# core09ss.net
KiCad netlist of a schematic drawn in EAGLE
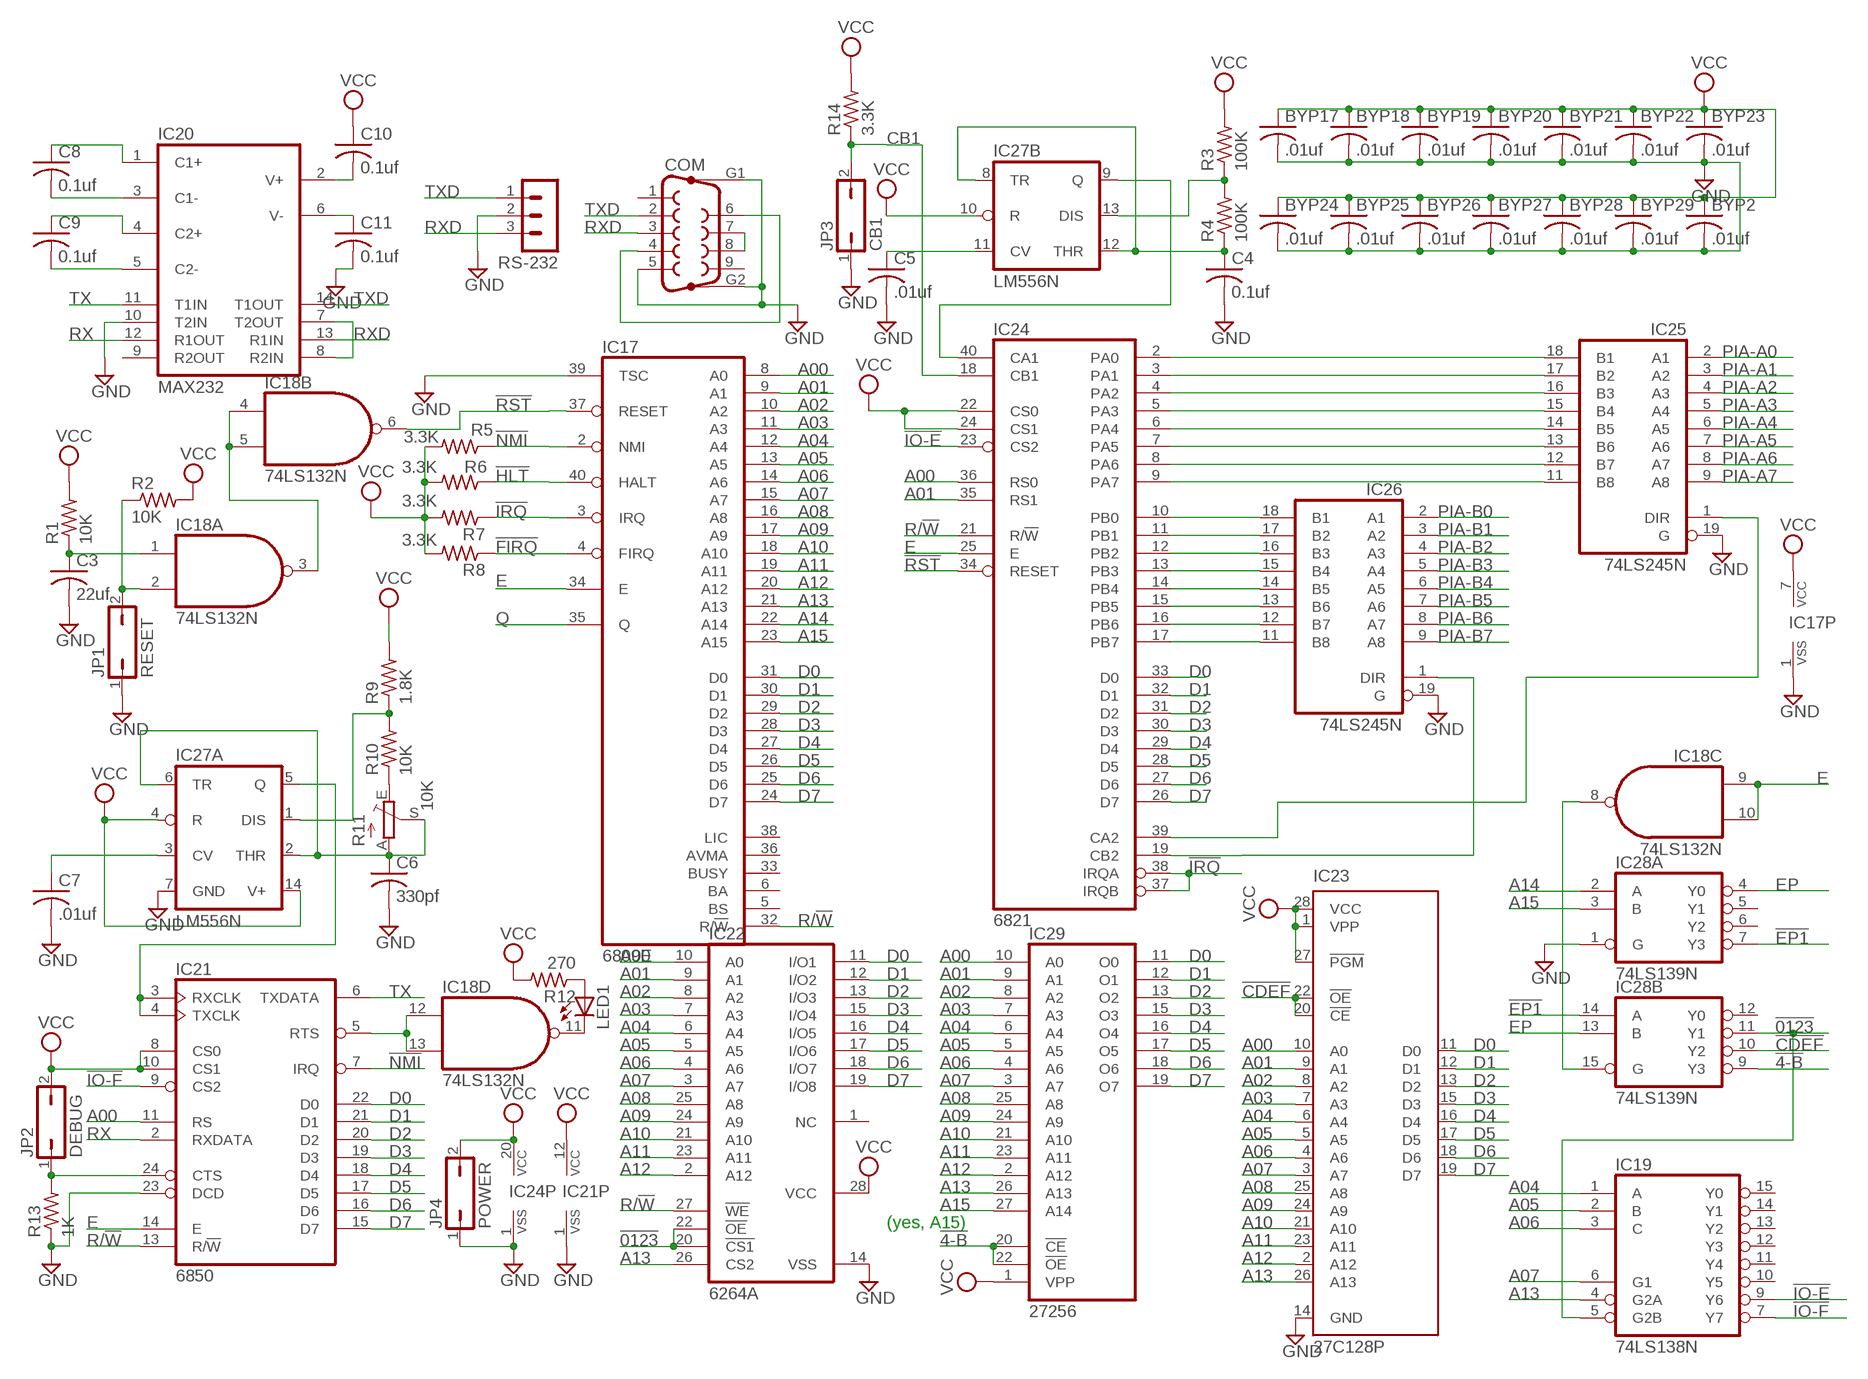
[diagram p0: schematic, sheet 1]
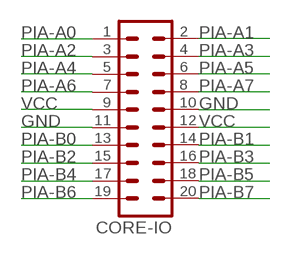
[diagram p1: schematic, sheet 2]
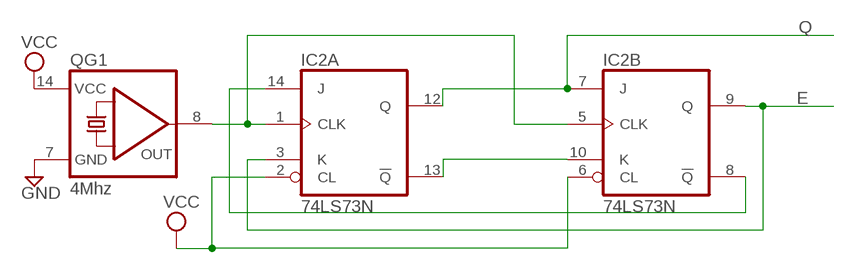
[diagram p2: schematic, sheet 3]

(export (version "E")
  (design (tool "Eeschema 10.0.6"))
  (components
    (comp (ref "IC2")
      (value "74LS73N")
      (footprint "eagle-import:DIL14")
      (libsource (lib "eagle-import") (part "7473NLS"))
    )
    (comp (ref "QG1")
      (value "4Mhz")
      (footprint "eagle-import:DIL14S")
      (libsource (lib "eagle-import") (part "QG5860"))
    )
    (comp (ref "BYP2")
      (value ".01uf")
      (footprint "eagle-import:C050-025X075")
      (libsource (lib "eagle-import") (part "C-US050-025X075"))
    )
    (comp (ref "BYP17")
      (value ".01uf")
      (footprint "eagle-import:C050-025X075")
      (libsource (lib "eagle-import") (part "C-US050-025X075"))
    )
    (comp (ref "BYP18")
      (value ".01uf")
      (footprint "eagle-import:C050-025X075")
      (libsource (lib "eagle-import") (part "C-US050-025X075"))
    )
    (comp (ref "BYP19")
      (value ".01uf")
      (footprint "eagle-import:C050-025X075")
      (libsource (lib "eagle-import") (part "C-US050-025X075"))
    )
    (comp (ref "BYP20")
      (value ".01uf")
      (footprint "eagle-import:C050-025X075")
      (libsource (lib "eagle-import") (part "C-US050-025X075"))
    )
    (comp (ref "BYP21")
      (value ".01uf")
      (footprint "eagle-import:C050-025X075")
      (libsource (lib "eagle-import") (part "C-US050-025X075"))
    )
    (comp (ref "BYP22")
      (value ".01uf")
      (footprint "eagle-import:C050-025X075")
      (libsource (lib "eagle-import") (part "C-US050-025X075"))
    )
    (comp (ref "BYP23")
      (value ".01uf")
      (footprint "eagle-import:C050-025X075")
      (libsource (lib "eagle-import") (part "C-US050-025X075"))
    )
    (comp (ref "BYP24")
      (value ".01uf")
      (footprint "eagle-import:C050-025X075")
      (libsource (lib "eagle-import") (part "C-US050-025X075"))
    )
    (comp (ref "BYP25")
      (value ".01uf")
      (footprint "eagle-import:C050-025X075")
      (libsource (lib "eagle-import") (part "C-US050-025X075"))
    )
    (comp (ref "BYP26")
      (value ".01uf")
      (footprint "eagle-import:C050-025X075")
      (libsource (lib "eagle-import") (part "C-US050-025X075"))
    )
    (comp (ref "BYP27")
      (value ".01uf")
      (footprint "eagle-import:C050-025X075")
      (libsource (lib "eagle-import") (part "C-US050-025X075"))
    )
    (comp (ref "BYP28")
      (value ".01uf")
      (footprint "eagle-import:C050-025X075")
      (libsource (lib "eagle-import") (part "C-US050-025X075"))
    )
    (comp (ref "BYP29")
      (value ".01uf")
      (footprint "eagle-import:C050-025X075")
      (libsource (lib "eagle-import") (part "C-US050-025X075"))
    )
    (comp (ref "C3")
      (value "22uf")
      (footprint "eagle-import:C102-043X133")
      (libsource (lib "eagle-import") (part "C-US102-043X133"))
    )
    (comp (ref "C4")
      (value "0.1uf")
      (footprint "eagle-import:C050-025X075")
      (libsource (lib "eagle-import") (part "C-US050-025X075"))
    )
    (comp (ref "C5")
      (value ".01uf")
      (footprint "eagle-import:C050-025X075")
      (libsource (lib "eagle-import") (part "C-US050-025X075"))
    )
    (comp (ref "C6")
      (value "330pf")
      (footprint "eagle-import:C050-025X075")
      (libsource (lib "eagle-import") (part "C-US050-025X075"))
    )
    (comp (ref "C7")
      (value ".01uf")
      (footprint "eagle-import:C050-025X075")
      (libsource (lib "eagle-import") (part "C-US050-025X075"))
    )
    (comp (ref "C8")
      (value "0.1uf")
      (footprint "eagle-import:C050-025X075")
      (libsource (lib "eagle-import") (part "C-US050-025X075"))
    )
    (comp (ref "C9")
      (value "0.1uf")
      (footprint "eagle-import:C050-025X075")
      (libsource (lib "eagle-import") (part "C-US050-025X075"))
    )
    (comp (ref "C10")
      (value "0.1uf")
      (footprint "eagle-import:C050-025X075")
      (libsource (lib "eagle-import") (part "C-US050-025X075"))
    )
    (comp (ref "C11")
      (value "0.1uf")
      (footprint "eagle-import:C050-025X075")
      (libsource (lib "eagle-import") (part "C-US050-025X075"))
    )
    (comp (ref "COM")
      (value "F09HP")
      (footprint "eagle-import:F09HP")
      (libsource (lib "eagle-import") (part "F09HP"))
    )
    (comp (ref "IC17")
      (value "6809E")
      (footprint "eagle-import:DIL40")
      (fields (field (name "MF") "NTE ELECTRONICS") (field (name "MPN") "NTE6809E"))
      (libsource (lib "eagle-import") (part "6809E"))
    )
    (comp (ref "IC18")
      (value "74LS132N")
      (footprint "eagle-import:DIL14")
      (libsource (lib "eagle-import") (part "7400NLS"))
    )
    (comp (ref "IC19")
      (value "74LS138N")
      (footprint "eagle-import:DIL16")
      (libsource (lib "eagle-import") (part "74138NLS"))
    )
    (comp (ref "IC20")
      (value "MAX232")
      (footprint "eagle-import:DIL16")
      (fields (field (name "MF") "MAXIM") (field (name "MPN") "MAX232ACPE+"))
      (libsource (lib "eagle-import") (part "MAX232"))
    )
    (comp (ref "IC21")
      (value "6850")
      (footprint "eagle-import:DIL24")
      (fields (field (name "MF") "NTE ELECTRONICS") (field (name "MPN") "NTE6850"))
      (libsource (lib "eagle-import") (part "6850"))
    )
    (comp (ref "IC22")
      (value "6264A")
      (footprint "eagle-import:DIL28-6")
      (libsource (lib "eagle-import") (part "6264A"))
    )
    (comp (ref "IC23")
      (value "27C128P")
      (footprint "eagle-import:DIL28-6")
      (libsource (lib "eagle-import") (part "27128PC"))
    )
    (comp (ref "IC24")
      (value "6821")
      (footprint "eagle-import:DIL40")
      (fields (field (name "MF") "NTE ELECTRONICS") (field (name "MPN") "NTE6821"))
      (libsource (lib "eagle-import") (part "6821"))
    )
    (comp (ref "IC25")
      (value "74LS245N")
      (footprint "eagle-import:DIL20")
      (libsource (lib "eagle-import") (part "74245NLS"))
    )
    (comp (ref "IC26")
      (value "74LS245N")
      (footprint "eagle-import:DIL20")
      (libsource (lib "eagle-import") (part "74245NLS"))
    )
    (comp (ref "IC27")
      (value "LM556N")
      (footprint "eagle-import:DIL14")
      (libsource (lib "eagle-import") (part "556NLM"))
    )
    (comp (ref "IC28")
      (value "74LS139N")
      (footprint "eagle-import:DIL16")
      (libsource (lib "eagle-import") (part "74139NLS"))
    )
    (comp (ref "IC29")
      (value "27256")
      (footprint "eagle-import:DIL28")
      (libsource (lib "eagle-import") (part "27256"))
    )
    (comp (ref "JP1")
      (value "RESET")
      (footprint "eagle-import:JP1")
      (libsource (lib "eagle-import") (part "JP1Q"))
    )
    (comp (ref "JP2")
      (value "DEBUG")
      (footprint "eagle-import:JP1")
      (libsource (lib "eagle-import") (part "JP1Q"))
    )
    (comp (ref "JP3")
      (value "CB1")
      (footprint "eagle-import:JP1")
      (libsource (lib "eagle-import") (part "JP1Q"))
    )
    (comp (ref "JP4")
      (value "POWER")
      (footprint "eagle-import:JP1")
      (libsource (lib "eagle-import") (part "JP1Q"))
    )
    (comp (ref "LED1")
      (value "LED3MM")
      (footprint "eagle-import:LED3MM")
      (libsource (lib "eagle-import") (part "LED3MM"))
    )
    (comp (ref "R1")
      (value "10K")
      (footprint "eagle-import:0207_7")
      (libsource (lib "eagle-import") (part "R-US_0207/7"))
    )
    (comp (ref "R2")
      (value "10K")
      (footprint "eagle-import:0207_7")
      (libsource (lib "eagle-import") (part "R-US_0207/7"))
    )
    (comp (ref "R3")
      (value "100K")
      (footprint "eagle-import:0207_7")
      (libsource (lib "eagle-import") (part "R-US_0207/7"))
    )
    (comp (ref "R4")
      (value "100K")
      (footprint "eagle-import:0207_7")
      (libsource (lib "eagle-import") (part "R-US_0207/7"))
    )
    (comp (ref "R5")
      (value "3.3K")
      (footprint "eagle-import:0207_7")
      (libsource (lib "eagle-import") (part "R-US_0207/7"))
    )
    (comp (ref "R6")
      (value "3.3K")
      (footprint "eagle-import:0207_7")
      (libsource (lib "eagle-import") (part "R-US_0207/7"))
    )
    (comp (ref "R7")
      (value "3.3K")
      (footprint "eagle-import:0207_7")
      (libsource (lib "eagle-import") (part "R-US_0207/7"))
    )
    (comp (ref "R8")
      (value "3.3K")
      (footprint "eagle-import:0207_7")
      (libsource (lib "eagle-import") (part "R-US_0207/7"))
    )
    (comp (ref "R9")
      (value "1.8K")
      (footprint "eagle-import:0207_7")
      (libsource (lib "eagle-import") (part "R-US_0207/7"))
    )
    (comp (ref "R10")
      (value "10K")
      (footprint "eagle-import:0207_7")
      (libsource (lib "eagle-import") (part "R-US_0207/7"))
    )
    (comp (ref "R11")
      (value "10K")
      (footprint "eagle-import:SP19L")
      (libsource (lib "eagle-import") (part "TRIM_EU-B90P"))
    )
    (comp (ref "R12")
      (value "270")
      (footprint "eagle-import:0207_7")
      (libsource (lib "eagle-import") (part "R-US_0207/7"))
    )
    (comp (ref "R13")
      (value "1K")
      (footprint "eagle-import:0207_7")
      (libsource (lib "eagle-import") (part "R-US_0207/7"))
    )
    (comp (ref "R14")
      (value "3.3K")
      (footprint "eagle-import:0207_7")
      (libsource (lib "eagle-import") (part "R-US_0207/7"))
    )
    (comp (ref "RS-232")
      (value "MA03-1")
      (footprint "eagle-import:MA03-1")
      (libsource (lib "eagle-import") (part "MA03-1"))
    )
    (comp (ref "CORE-IO")
      (value "MA10-2")
      (footprint "eagle-import:MA10-2")
      (libsource (lib "eagle-import") (part "MA10-2"))
    )
  )
  (nets
    (net (code "1") (name "A00") (class "Default")
      (node (ref "IC17") (pin "8") (pinfunction "A0_8") (pintype "tri_state"))
      (node (ref "IC21") (pin "11") (pinfunction "RS_11") (pintype "input"))
      (node (ref "IC22") (pin "10") (pinfunction "A0_10") (pintype "input"))
      (node (ref "IC23") (pin "10") (pinfunction "A0_10") (pintype "input"))
      (node (ref "IC24") (pin "36") (pinfunction "RS0_36") (pintype "input"))
      (node (ref "IC29") (pin "10") (pinfunction "A0_10") (pintype "input"))
    )
    (net (code "2") (name "A01") (class "Default")
      (node (ref "IC17") (pin "9") (pinfunction "A1_9") (pintype "tri_state"))
      (node (ref "IC22") (pin "9") (pinfunction "A1_9") (pintype "input"))
      (node (ref "IC23") (pin "9") (pinfunction "A1_9") (pintype "input"))
      (node (ref "IC24") (pin "35") (pinfunction "RS1_35") (pintype "input"))
      (node (ref "IC29") (pin "9") (pinfunction "A1_9") (pintype "input"))
    )
    (net (code "3") (name "A02") (class "Default")
      (node (ref "IC17") (pin "10") (pinfunction "A2_10") (pintype "tri_state"))
      (node (ref "IC22") (pin "8") (pinfunction "A2_8") (pintype "input"))
      (node (ref "IC23") (pin "8") (pinfunction "A2_8") (pintype "input"))
      (node (ref "IC29") (pin "8") (pinfunction "A2_8") (pintype "input"))
    )
    (net (code "4") (name "A03") (class "Default")
      (node (ref "IC17") (pin "11") (pinfunction "A3_11") (pintype "tri_state"))
      (node (ref "IC22") (pin "7") (pinfunction "A3_7") (pintype "input"))
      (node (ref "IC23") (pin "7") (pinfunction "A3_7") (pintype "input"))
      (node (ref "IC29") (pin "7") (pinfunction "A3_7") (pintype "input"))
    )
    (net (code "5") (name "A04") (class "Default")
      (node (ref "IC17") (pin "12") (pinfunction "A4_12") (pintype "tri_state"))
      (node (ref "IC19") (pin "1") (pinfunction "A_1") (pintype "input"))
      (node (ref "IC22") (pin "6") (pinfunction "A4_6") (pintype "input"))
      (node (ref "IC23") (pin "6") (pinfunction "A4_6") (pintype "input"))
      (node (ref "IC29") (pin "6") (pinfunction "A4_6") (pintype "input"))
    )
    (net (code "6") (name "A05") (class "Default")
      (node (ref "IC17") (pin "13") (pinfunction "A5_13") (pintype "tri_state"))
      (node (ref "IC19") (pin "2") (pinfunction "B_2") (pintype "input"))
      (node (ref "IC22") (pin "5") (pinfunction "A5_5") (pintype "input"))
      (node (ref "IC23") (pin "5") (pinfunction "A5_5") (pintype "input"))
      (node (ref "IC29") (pin "5") (pinfunction "A5_5") (pintype "input"))
    )
    (net (code "7") (name "A06") (class "Default")
      (node (ref "IC17") (pin "14") (pinfunction "A6_14") (pintype "tri_state"))
      (node (ref "IC19") (pin "3") (pinfunction "C_3") (pintype "input"))
      (node (ref "IC22") (pin "4") (pinfunction "A6_4") (pintype "input"))
      (node (ref "IC23") (pin "4") (pinfunction "A6_4") (pintype "input"))
      (node (ref "IC29") (pin "4") (pinfunction "A6_4") (pintype "input"))
    )
    (net (code "8") (name "A07") (class "Default")
      (node (ref "IC17") (pin "15") (pinfunction "A7_15") (pintype "tri_state"))
      (node (ref "IC19") (pin "6") (pinfunction "G1_6") (pintype "input"))
      (node (ref "IC22") (pin "3") (pinfunction "A7_3") (pintype "input"))
      (node (ref "IC23") (pin "3") (pinfunction "A7_3") (pintype "input"))
      (node (ref "IC29") (pin "3") (pinfunction "A7_3") (pintype "input"))
    )
    (net (code "9") (name "A08") (class "Default")
      (node (ref "IC17") (pin "16") (pinfunction "A8_16") (pintype "tri_state"))
      (node (ref "IC22") (pin "25") (pinfunction "A8_25") (pintype "input"))
      (node (ref "IC23") (pin "25") (pinfunction "A8_25") (pintype "input"))
      (node (ref "IC29") (pin "25") (pinfunction "A8_25") (pintype "input"))
    )
    (net (code "10") (name "A09") (class "Default")
      (node (ref "IC17") (pin "17") (pinfunction "A9_17") (pintype "tri_state"))
      (node (ref "IC22") (pin "24") (pinfunction "A9_24") (pintype "input"))
      (node (ref "IC23") (pin "24") (pinfunction "A9_24") (pintype "input"))
      (node (ref "IC29") (pin "24") (pinfunction "A9_24") (pintype "input"))
    )
    (net (code "11") (name "A10") (class "Default")
      (node (ref "IC17") (pin "18") (pinfunction "A10_18") (pintype "tri_state"))
      (node (ref "IC22") (pin "21") (pinfunction "A10_21") (pintype "input"))
      (node (ref "IC23") (pin "21") (pinfunction "A10_21") (pintype "input"))
      (node (ref "IC29") (pin "21") (pinfunction "A10_21") (pintype "input"))
    )
    (net (code "12") (name "A11") (class "Default")
      (node (ref "IC17") (pin "19") (pinfunction "A11_19") (pintype "tri_state"))
      (node (ref "IC22") (pin "23") (pinfunction "A11_23") (pintype "input"))
      (node (ref "IC23") (pin "23") (pinfunction "A11_23") (pintype "input"))
      (node (ref "IC29") (pin "23") (pinfunction "A11_23") (pintype "input"))
    )
    (net (code "13") (name "A12") (class "Default")
      (node (ref "IC17") (pin "20") (pinfunction "A12_20") (pintype "tri_state"))
      (node (ref "IC22") (pin "2") (pinfunction "A12_2") (pintype "input"))
      (node (ref "IC23") (pin "2") (pinfunction "A12_2") (pintype "input"))
      (node (ref "IC29") (pin "2") (pinfunction "A12_2") (pintype "input"))
    )
    (net (code "14") (name "A13") (class "Default")
      (node (ref "IC17") (pin "21") (pinfunction "A13_21") (pintype "tri_state"))
      (node (ref "IC19") (pin "4") (pinfunction "G2A_4") (pintype "input"))
      (node (ref "IC22") (pin "26") (pinfunction "CS2_26") (pintype "input"))
      (node (ref "IC23") (pin "26") (pinfunction "A13_26") (pintype "input"))
      (node (ref "IC29") (pin "26") (pinfunction "A13_26") (pintype "input"))
    )
    (net (code "15") (name "A14") (class "Default")
      (node (ref "IC17") (pin "22") (pinfunction "A14_22") (pintype "tri_state"))
      (node (ref "IC28") (pin "2") (pinfunction "A_2") (pintype "input"))
    )
    (net (code "16") (name "A15") (class "Default")
      (node (ref "IC17") (pin "23") (pinfunction "A15_23") (pintype "tri_state"))
      (node (ref "IC28") (pin "3") (pinfunction "B_3") (pintype "input"))
      (node (ref "IC29") (pin "27") (pinfunction "A14_27") (pintype "input"))
    )
    (net (code "17") (name "CB1") (class "Default")
      (node (ref "IC24") (pin "18") (pinfunction "CB1_18") (pintype "input"))
      (node (ref "JP3") (pin "2") (pinfunction "2_2") (pintype "passive"))
      (node (ref "R14") (pin "1") (pinfunction "1_1") (pintype "passive"))
    )
    (net (code "18") (name "D0") (class "Default")
      (node (ref "IC17") (pin "31") (pinfunction "D0_31") (pintype "bidirectional"))
      (node (ref "IC21") (pin "22") (pinfunction "D0_22") (pintype "bidirectional"))
      (node (ref "IC22") (pin "11") (pinfunction "I/O1_11") (pintype "bidirectional"))
      (node (ref "IC23") (pin "11") (pinfunction "D0_11") (pintype "tri_state"))
      (node (ref "IC24") (pin "33") (pinfunction "D0_33") (pintype "bidirectional"))
      (node (ref "IC29") (pin "11") (pinfunction "O0_11") (pintype "tri_state"))
    )
    (net (code "19") (name "D1") (class "Default")
      (node (ref "IC17") (pin "30") (pinfunction "D1_30") (pintype "bidirectional"))
      (node (ref "IC21") (pin "21") (pinfunction "D1_21") (pintype "bidirectional"))
      (node (ref "IC22") (pin "12") (pinfunction "I/O2_12") (pintype "bidirectional"))
      (node (ref "IC23") (pin "12") (pinfunction "D1_12") (pintype "tri_state"))
      (node (ref "IC24") (pin "32") (pinfunction "D1_32") (pintype "bidirectional"))
      (node (ref "IC29") (pin "12") (pinfunction "O1_12") (pintype "tri_state"))
    )
    (net (code "20") (name "D2") (class "Default")
      (node (ref "IC17") (pin "29") (pinfunction "D2_29") (pintype "bidirectional"))
      (node (ref "IC21") (pin "20") (pinfunction "D2_20") (pintype "bidirectional"))
      (node (ref "IC22") (pin "13") (pinfunction "I/O3_13") (pintype "bidirectional"))
      (node (ref "IC23") (pin "13") (pinfunction "D2_13") (pintype "tri_state"))
      (node (ref "IC24") (pin "31") (pinfunction "D2_31") (pintype "bidirectional"))
      (node (ref "IC29") (pin "13") (pinfunction "O2_13") (pintype "tri_state"))
    )
    (net (code "21") (name "D3") (class "Default")
      (node (ref "IC17") (pin "28") (pinfunction "D3_28") (pintype "bidirectional"))
      (node (ref "IC21") (pin "19") (pinfunction "D3_19") (pintype "bidirectional"))
      (node (ref "IC22") (pin "15") (pinfunction "I/O4_15") (pintype "bidirectional"))
      (node (ref "IC23") (pin "15") (pinfunction "D3_15") (pintype "tri_state"))
      (node (ref "IC24") (pin "30") (pinfunction "D3_30") (pintype "bidirectional"))
      (node (ref "IC29") (pin "15") (pinfunction "O3_15") (pintype "tri_state"))
    )
    (net (code "22") (name "D4") (class "Default")
      (node (ref "IC17") (pin "27") (pinfunction "D4_27") (pintype "bidirectional"))
      (node (ref "IC21") (pin "18") (pinfunction "D4_18") (pintype "bidirectional"))
      (node (ref "IC22") (pin "16") (pinfunction "I/O5_16") (pintype "bidirectional"))
      (node (ref "IC23") (pin "16") (pinfunction "D4_16") (pintype "tri_state"))
      (node (ref "IC24") (pin "29") (pinfunction "D4_29") (pintype "bidirectional"))
      (node (ref "IC29") (pin "16") (pinfunction "O4_16") (pintype "tri_state"))
    )
    (net (code "23") (name "D5") (class "Default")
      (node (ref "IC17") (pin "26") (pinfunction "D5_26") (pintype "bidirectional"))
      (node (ref "IC21") (pin "17") (pinfunction "D5_17") (pintype "bidirectional"))
      (node (ref "IC22") (pin "17") (pinfunction "I/O6_17") (pintype "bidirectional"))
      (node (ref "IC23") (pin "17") (pinfunction "D5_17") (pintype "tri_state"))
      (node (ref "IC24") (pin "28") (pinfunction "D5_28") (pintype "bidirectional"))
      (node (ref "IC29") (pin "17") (pinfunction "O5_17") (pintype "tri_state"))
    )
    (net (code "24") (name "D6") (class "Default")
      (node (ref "IC17") (pin "25") (pinfunction "D6_25") (pintype "bidirectional"))
      (node (ref "IC21") (pin "16") (pinfunction "D6_16") (pintype "bidirectional"))
      (node (ref "IC22") (pin "18") (pinfunction "I/O7_18") (pintype "bidirectional"))
      (node (ref "IC23") (pin "18") (pinfunction "D6_18") (pintype "tri_state"))
      (node (ref "IC24") (pin "27") (pinfunction "D6_27") (pintype "bidirectional"))
      (node (ref "IC29") (pin "18") (pinfunction "O6_18") (pintype "tri_state"))
    )
    (net (code "25") (name "D7") (class "Default")
      (node (ref "IC17") (pin "24") (pinfunction "D7_24") (pintype "bidirectional"))
      (node (ref "IC21") (pin "15") (pinfunction "D7_15") (pintype "bidirectional"))
      (node (ref "IC22") (pin "19") (pinfunction "I/O8_19") (pintype "bidirectional"))
      (node (ref "IC23") (pin "19") (pinfunction "D7_19") (pintype "tri_state"))
      (node (ref "IC24") (pin "26") (pinfunction "D7_26") (pintype "bidirectional"))
      (node (ref "IC29") (pin "19") (pinfunction "O7_19") (pintype "tri_state"))
    )
    (net (code "26") (name "E") (class "Default")
      (node (ref "IC17") (pin "34") (pinfunction "E_34") (pintype "input"))
      (node (ref "IC18") (pin "10") (pinfunction "I1_10") (pintype "input"))
      (node (ref "IC18") (pin "9") (pinfunction "I0_9") (pintype "input"))
      (node (ref "IC2") (pin "3") (pinfunction "K_3") (pintype "input"))
      (node (ref "IC2") (pin "9") (pinfunction "Q_9") (pintype "output"))
      (node (ref "IC21") (pin "14") (pinfunction "E_14") (pintype "input"))
      (node (ref "IC24") (pin "25") (pinfunction "E_25") (pintype "input"))
    )
    (net (code "27") (name "EP") (class "Default")
      (node (ref "IC28") (pin "13") (pinfunction "B_13") (pintype "input"))
      (node (ref "IC28") (pin "4") (pinfunction "Y0_4") (pintype "output"))
    )
    (net (code "28") (name "GND") (class "Default")
      (node (ref "BYP17") (pin "2") (pinfunction "2_2") (pintype "passive"))
      (node (ref "BYP18") (pin "2") (pinfunction "2_2") (pintype "passive"))
      (node (ref "BYP19") (pin "2") (pinfunction "2_2") (pintype "passive"))
      (node (ref "BYP2") (pin "2") (pinfunction "2_2") (pintype "passive"))
      (node (ref "BYP20") (pin "2") (pinfunction "2_2") (pintype "passive"))
      (node (ref "BYP21") (pin "2") (pinfunction "2_2") (pintype "passive"))
      (node (ref "BYP22") (pin "2") (pinfunction "2_2") (pintype "passive"))
      (node (ref "BYP23") (pin "2") (pinfunction "2_2") (pintype "passive"))
      (node (ref "BYP24") (pin "2") (pinfunction "2_2") (pintype "passive"))
      (node (ref "BYP25") (pin "2") (pinfunction "2_2") (pintype "passive"))
      (node (ref "BYP26") (pin "2") (pinfunction "2_2") (pintype "passive"))
      (node (ref "BYP27") (pin "2") (pinfunction "2_2") (pintype "passive"))
      (node (ref "BYP28") (pin "2") (pinfunction "2_2") (pintype "passive"))
      (node (ref "BYP29") (pin "2") (pinfunction "2_2") (pintype "passive"))
      (node (ref "C11") (pin "2") (pinfunction "2_2") (pintype "passive"))
      (node (ref "C3") (pin "2") (pinfunction "2_2") (pintype "passive"))
      (node (ref "C4") (pin "2") (pinfunction "2_2") (pintype "passive"))
      (node (ref "C5") (pin "2") (pinfunction "2_2") (pintype "passive"))
      (node (ref "C6") (pin "2") (pinfunction "2_2") (pintype "passive"))
      (node (ref "C7") (pin "2") (pinfunction "2_2") (pintype "passive"))
      (node (ref "COM") (pin "5") (pinfunction "5_5") (pintype "passive"))
      (node (ref "COM") (pin "G1") (pinfunction "G1_G1") (pintype "passive"))
      (node (ref "COM") (pin "G2") (pinfunction "G2_G2") (pintype "passive"))
      (node (ref "CORE-IO") (pin "10") (pinfunction "10_10") (pintype "passive"))
      (node (ref "CORE-IO") (pin "11") (pinfunction "11_11") (pintype "passive"))
      (node (ref "IC17") (pin "1") (pinfunction "VSS_1") (pintype "power_in"))
      (node (ref "IC17") (pin "39") (pinfunction "TSC_39") (pintype "input"))
      (node (ref "IC20") (pin "10") (pinfunction "T2IN_10") (pintype "input"))
      (node (ref "IC21") (pin "1") (pinfunction "VSS_1") (pintype "power_in"))
      (node (ref "IC21") (pin "23") (pinfunction "DCD_23") (pintype "input"))
      (node (ref "IC22") (pin "14") (pinfunction "VSS_14") (pintype "power_in"))
      (node (ref "IC23") (pin "14") (pinfunction "GND_14") (pintype "power_in"))
      (node (ref "IC24") (pin "1") (pinfunction "VSS_1") (pintype "power_in"))
      (node (ref "IC25") (pin "19") (pinfunction "G_19") (pintype "input"))
      (node (ref "IC26") (pin "19") (pinfunction "G_19") (pintype "input"))
      (node (ref "IC27") (pin "7") (pinfunction "GND_7") (pintype "power_in"))
      (node (ref "IC28") (pin "1") (pinfunction "G_1") (pintype "input"))
      (node (ref "JP1") (pin "1") (pinfunction "1_1") (pintype "passive"))
      (node (ref "JP3") (pin "1") (pinfunction "1_1") (pintype "passive"))
      (node (ref "JP4") (pin "1") (pinfunction "1_1") (pintype "passive"))
      (node (ref "QG1") (pin "7") (pinfunction "GND_7") (pintype "power_in"))
      (node (ref "R13") (pin "1") (pinfunction "1_1") (pintype "passive"))
      (node (ref "RS-232") (pin "2") (pinfunction "2_2") (pintype "passive"))
    )
    (net (code "29") (name "Net-(COM-Pad4)") (class "Default")
      (node (ref "COM") (pin "4") (pinfunction "4_4") (pintype "passive"))
      (node (ref "COM") (pin "6") (pinfunction "6_6") (pintype "passive"))
    )
    (net (code "30") (name "Net-(COM-Pad7)") (class "Default")
      (node (ref "COM") (pin "7") (pinfunction "7_7") (pintype "passive"))
      (node (ref "COM") (pin "8") (pinfunction "8_8") (pintype "passive"))
    )
    (net (code "31") (name "Net-(IC2A-CLK)") (class "Default")
      (node (ref "IC2") (pin "1") (pinfunction "CLK_1") (pintype "input"))
      (node (ref "IC2") (pin "5") (pinfunction "CLK_5") (pintype "input"))
      (node (ref "QG1") (pin "8") (pinfunction "OUT_8") (pintype "output"))
    )
    (net (code "32") (name "Net-(IC2A-J)") (class "Default")
      (node (ref "IC2") (pin "14") (pinfunction "J_14") (pintype "input"))
      (node (ref "IC2") (pin "8") (pinfunction "~{Q}_8") (pintype "output"))
    )
    (net (code "33") (name "Net-(IC2A-~{Q})") (class "Default")
      (node (ref "IC2") (pin "10") (pinfunction "K_10") (pintype "input"))
      (node (ref "IC2") (pin "13") (pinfunction "~{Q}_13") (pintype "output"))
    )
    (net (code "34") (name "Net-(IC18A-I0)") (class "Default")
      (node (ref "C3") (pin "1") (pinfunction "1_1") (pintype "passive"))
      (node (ref "IC18") (pin "1") (pinfunction "I0_1") (pintype "input"))
      (node (ref "R1") (pin "1") (pinfunction "1_1") (pintype "passive"))
    )
    (net (code "35") (name "Net-(IC18A-I1)") (class "Default")
      (node (ref "IC18") (pin "2") (pinfunction "I1_2") (pintype "input"))
      (node (ref "JP1") (pin "2") (pinfunction "2_2") (pintype "passive"))
      (node (ref "R2") (pin "1") (pinfunction "1_1") (pintype "passive"))
    )
    (net (code "36") (name "Net-(IC18A-O)") (class "Default")
      (node (ref "IC18") (pin "3") (pinfunction "O_3") (pintype "output"))
      (node (ref "IC18") (pin "4") (pinfunction "I0_4") (pintype "input"))
      (node (ref "IC18") (pin "5") (pinfunction "I1_5") (pintype "input"))
    )
    (net (code "37") (name "Net-(IC18C-O)") (class "Default")
      (node (ref "IC18") (pin "8") (pinfunction "O_8") (pintype "output"))
      (node (ref "IC28") (pin "15") (pinfunction "G_15") (pintype "input"))
    )
    (net (code "38") (name "Net-(IC18D-I0)") (class "Default")
      (node (ref "IC18") (pin "12") (pinfunction "I0_12") (pintype "input"))
      (node (ref "IC18") (pin "13") (pinfunction "I1_13") (pintype "input"))
      (node (ref "IC21") (pin "5") (pinfunction "RTS_5") (pintype "output"))
    )
    (net (code "39") (name "Net-(IC18D-O)") (class "Default")
      (node (ref "IC18") (pin "11") (pinfunction "O_11") (pintype "output"))
      (node (ref "LED1") (pin "K") (pinfunction "C_K") (pintype "passive"))
    )
    (net (code "40") (name "Net-(IC20A-C1+)") (class "Default")
      (node (ref "C8") (pin "1") (pinfunction "1_1") (pintype "passive"))
      (node (ref "IC20") (pin "1") (pinfunction "C1+_1") (pintype "bidirectional"))
    )
    (net (code "41") (name "Net-(IC20A-C1-)") (class "Default")
      (node (ref "C8") (pin "2") (pinfunction "2_2") (pintype "passive"))
      (node (ref "IC20") (pin "3") (pinfunction "C1-_3") (pintype "bidirectional"))
    )
    (net (code "42") (name "Net-(IC20A-C2+)") (class "Default")
      (node (ref "C9") (pin "1") (pinfunction "1_1") (pintype "passive"))
      (node (ref "IC20") (pin "4") (pinfunction "C2+_4") (pintype "bidirectional"))
    )
    (net (code "43") (name "Net-(IC20A-C2-)") (class "Default")
      (node (ref "C9") (pin "2") (pinfunction "2_2") (pintype "passive"))
      (node (ref "IC20") (pin "5") (pinfunction "C2-_5") (pintype "bidirectional"))
    )
    (net (code "44") (name "Net-(IC20A-R2IN)") (class "Default")
      (node (ref "IC20") (pin "7") (pinfunction "T2OUT_7") (pintype "output"))
      (node (ref "IC20") (pin "8") (pinfunction "R2IN_8") (pintype "input"))
    )
    (net (code "45") (name "Net-(IC20A-V+)") (class "Default")
      (node (ref "C10") (pin "2") (pinfunction "2_2") (pintype "passive"))
      (node (ref "IC20") (pin "2") (pinfunction "V+_2") (pintype "bidirectional"))
    )
    (net (code "46") (name "Net-(IC20A-V-)") (class "Default")
      (node (ref "C11") (pin "1") (pinfunction "1_1") (pintype "passive"))
      (node (ref "IC20") (pin "6") (pinfunction "V-_6") (pintype "bidirectional"))
    )
    (net (code "47") (name "Net-(IC21A-CTS)") (class "Default")
      (node (ref "IC21") (pin "24") (pinfunction "CTS_24") (pintype "input"))
      (node (ref "JP2") (pin "1") (pinfunction "1_1") (pintype "passive"))
      (node (ref "R13") (pin "2") (pinfunction "2_2") (pintype "passive"))
    )
    (net (code "48") (name "Net-(IC21A-RXCLK)") (class "Default")
      (node (ref "IC21") (pin "3") (pinfunction "RXCLK_3") (pintype "input"))
      (node (ref "IC21") (pin "4") (pinfunction "TXCLK_4") (pintype "input"))
      (node (ref "IC27") (pin "5") (pinfunction "Q_5") (pintype "output"))
    )
    (net (code "49") (name "Net-(IC24A-CA1)") (class "Default")
      (node (ref "IC24") (pin "40") (pinfunction "CA1_40") (pintype "input"))
      (node (ref "IC27") (pin "9") (pinfunction "Q_9") (pintype "output"))
    )
    (net (code "50") (name "Net-(IC24A-CA2)") (class "Default")
      (node (ref "IC24") (pin "39") (pinfunction "CA2_39") (pintype "bidirectional"))
      (node (ref "IC25") (pin "1") (pinfunction "DIR_1") (pintype "input"))
    )
    (net (code "51") (name "Net-(IC24A-CB2)") (class "Default")
      (node (ref "IC24") (pin "19") (pinfunction "CB2_19") (pintype "bidirectional"))
      (node (ref "IC26") (pin "1") (pinfunction "DIR_1") (pintype "input"))
    )
    (net (code "52") (name "Net-(IC24A-PA0)") (class "Default")
      (node (ref "IC24") (pin "2") (pinfunction "PA0_2") (pintype "bidirectional"))
      (node (ref "IC25") (pin "18") (pinfunction "B1_18") (pintype "bidirectional"))
    )
    (net (code "53") (name "Net-(IC24A-PA1)") (class "Default")
      (node (ref "IC24") (pin "3") (pinfunction "PA1_3") (pintype "bidirectional"))
      (node (ref "IC25") (pin "17") (pinfunction "B2_17") (pintype "bidirectional"))
    )
    (net (code "54") (name "Net-(IC24A-PA2)") (class "Default")
      (node (ref "IC24") (pin "4") (pinfunction "PA2_4") (pintype "bidirectional"))
      (node (ref "IC25") (pin "16") (pinfunction "B3_16") (pintype "bidirectional"))
    )
    (net (code "55") (name "Net-(IC24A-PA3)") (class "Default")
      (node (ref "IC24") (pin "5") (pinfunction "PA3_5") (pintype "bidirectional"))
      (node (ref "IC25") (pin "15") (pinfunction "B4_15") (pintype "bidirectional"))
    )
    (net (code "56") (name "Net-(IC24A-PA4)") (class "Default")
      (node (ref "IC24") (pin "6") (pinfunction "PA4_6") (pintype "bidirectional"))
      (node (ref "IC25") (pin "14") (pinfunction "B5_14") (pintype "bidirectional"))
    )
    (net (code "57") (name "Net-(IC24A-PA5)") (class "Default")
      (node (ref "IC24") (pin "7") (pinfunction "PA5_7") (pintype "bidirectional"))
      (node (ref "IC25") (pin "13") (pinfunction "B6_13") (pintype "bidirectional"))
    )
    (net (code "58") (name "Net-(IC24A-PA6)") (class "Default")
      (node (ref "IC24") (pin "8") (pinfunction "PA6_8") (pintype "bidirectional"))
      (node (ref "IC25") (pin "12") (pinfunction "B7_12") (pintype "bidirectional"))
    )
    (net (code "59") (name "Net-(IC24A-PA7)") (class "Default")
      (node (ref "IC24") (pin "9") (pinfunction "PA7_9") (pintype "bidirectional"))
      (node (ref "IC25") (pin "11") (pinfunction "B8_11") (pintype "bidirectional"))
    )
    (net (code "60") (name "Net-(IC24A-PB0)") (class "Default")
      (node (ref "IC24") (pin "10") (pinfunction "PB0_10") (pintype "bidirectional"))
      (node (ref "IC26") (pin "18") (pinfunction "B1_18") (pintype "bidirectional"))
    )
    (net (code "61") (name "Net-(IC24A-PB1)") (class "Default")
      (node (ref "IC24") (pin "11") (pinfunction "PB1_11") (pintype "bidirectional"))
      (node (ref "IC26") (pin "17") (pinfunction "B2_17") (pintype "bidirectional"))
    )
    (net (code "62") (name "Net-(IC24A-PB2)") (class "Default")
      (node (ref "IC24") (pin "12") (pinfunction "PB2_12") (pintype "bidirectional"))
      (node (ref "IC26") (pin "16") (pinfunction "B3_16") (pintype "bidirectional"))
    )
    (net (code "63") (name "Net-(IC24A-PB3)") (class "Default")
      (node (ref "IC24") (pin "13") (pinfunction "PB3_13") (pintype "bidirectional"))
      (node (ref "IC26") (pin "15") (pinfunction "B4_15") (pintype "bidirectional"))
    )
    (net (code "64") (name "Net-(IC24A-PB4)") (class "Default")
      (node (ref "IC24") (pin "14") (pinfunction "PB4_14") (pintype "bidirectional"))
      (node (ref "IC26") (pin "14") (pinfunction "B5_14") (pintype "bidirectional"))
    )
    (net (code "65") (name "Net-(IC24A-PB5)") (class "Default")
      (node (ref "IC24") (pin "15") (pinfunction "PB5_15") (pintype "bidirectional"))
      (node (ref "IC26") (pin "13") (pinfunction "B6_13") (pintype "bidirectional"))
    )
    (net (code "66") (name "Net-(IC24A-PB6)") (class "Default")
      (node (ref "IC24") (pin "16") (pinfunction "PB6_16") (pintype "bidirectional"))
      (node (ref "IC26") (pin "12") (pinfunction "B7_12") (pintype "bidirectional"))
    )
    (net (code "67") (name "Net-(IC24A-PB7)") (class "Default")
      (node (ref "IC24") (pin "17") (pinfunction "PB7_17") (pintype "bidirectional"))
      (node (ref "IC26") (pin "11") (pinfunction "B8_11") (pintype "bidirectional"))
    )
    (net (code "68") (name "Net-(IC27A-CV)") (class "Default")
      (node (ref "C7") (pin "1") (pinfunction "1_1") (pintype "passive"))
      (node (ref "IC27") (pin "3") (pinfunction "CV_3") (pintype "input"))
    )
    (net (code "69") (name "Net-(IC27A-DIS)") (class "Default")
      (node (ref "IC27") (pin "1") (pinfunction "DIS_1") (pintype "input"))
      (node (ref "R10") (pin "2") (pinfunction "2_2") (pintype "passive"))
      (node (ref "R9") (pin "1") (pinfunction "1_1") (pintype "passive"))
    )
    (net (code "70") (name "Net-(IC27A-THR)") (class "Default")
      (node (ref "C6") (pin "1") (pinfunction "1_1") (pintype "passive"))
      (node (ref "IC27") (pin "2") (pinfunction "THR_2") (pintype "input"))
      (node (ref "IC27") (pin "6") (pinfunction "TR_6") (pintype "input"))
      (node (ref "R11") (pin "A") (pinfunction "A_A") (pintype "passive"))
      (node (ref "R11") (pin "S") (pinfunction "S_S") (pintype "passive"))
    )
    (net (code "71") (name "Net-(IC27B-CV)") (class "Default")
      (node (ref "C5") (pin "1") (pinfunction "1_1") (pintype "passive"))
      (node (ref "IC27") (pin "11") (pinfunction "CV_11") (pintype "input"))
    )
    (net (code "72") (name "Net-(IC27B-DIS)") (class "Default")
      (node (ref "IC27") (pin "13") (pinfunction "DIS_13") (pintype "input"))
      (node (ref "R3") (pin "1") (pinfunction "1_1") (pintype "passive"))
      (node (ref "R4") (pin "2") (pinfunction "2_2") (pintype "passive"))
    )
    (net (code "73") (name "Net-(IC27B-THR)") (class "Default")
      (node (ref "C4") (pin "1") (pinfunction "1_1") (pintype "passive"))
      (node (ref "IC27") (pin "12") (pinfunction "THR_12") (pintype "input"))
      (node (ref "IC27") (pin "8") (pinfunction "TR_8") (pintype "input"))
      (node (ref "R4") (pin "1") (pinfunction "1_1") (pintype "passive"))
    )
    (net (code "74") (name "Net-(LED1-PadA)") (class "Default")
      (node (ref "LED1") (pin "A") (pinfunction "A_A") (pintype "passive"))
      (node (ref "R12") (pin "1") (pinfunction "1_1") (pintype "passive"))
    )
    (net (code "75") (name "Net-(R10-Pad1)") (class "Default")
      (node (ref "R10") (pin "1") (pinfunction "1_1") (pintype "passive"))
      (node (ref "R11") (pin "E") (pinfunction "E_E") (pintype "passive"))
    )
    (net (code "76") (name "PIA-A0") (class "Default")
      (node (ref "CORE-IO") (pin "1") (pinfunction "1_1") (pintype "passive"))
      (node (ref "IC25") (pin "2") (pinfunction "A1_2") (pintype "bidirectional"))
    )
    (net (code "77") (name "PIA-A1") (class "Default")
      (node (ref "CORE-IO") (pin "2") (pinfunction "2_2") (pintype "passive"))
      (node (ref "IC25") (pin "3") (pinfunction "A2_3") (pintype "bidirectional"))
    )
    (net (code "78") (name "PIA-A2") (class "Default")
      (node (ref "CORE-IO") (pin "3") (pinfunction "3_3") (pintype "passive"))
      (node (ref "IC25") (pin "4") (pinfunction "A3_4") (pintype "bidirectional"))
    )
    (net (code "79") (name "PIA-A3") (class "Default")
      (node (ref "CORE-IO") (pin "4") (pinfunction "4_4") (pintype "passive"))
      (node (ref "IC25") (pin "5") (pinfunction "A4_5") (pintype "bidirectional"))
    )
    (net (code "80") (name "PIA-A4") (class "Default")
      (node (ref "CORE-IO") (pin "5") (pinfunction "5_5") (pintype "passive"))
      (node (ref "IC25") (pin "6") (pinfunction "A5_6") (pintype "bidirectional"))
    )
    (net (code "81") (name "PIA-A5") (class "Default")
      (node (ref "CORE-IO") (pin "6") (pinfunction "6_6") (pintype "passive"))
      (node (ref "IC25") (pin "7") (pinfunction "A6_7") (pintype "bidirectional"))
    )
    (net (code "82") (name "PIA-A6") (class "Default")
      (node (ref "CORE-IO") (pin "7") (pinfunction "7_7") (pintype "passive"))
      (node (ref "IC25") (pin "8") (pinfunction "A7_8") (pintype "bidirectional"))
    )
    (net (code "83") (name "PIA-A7") (class "Default")
      (node (ref "CORE-IO") (pin "8") (pinfunction "8_8") (pintype "passive"))
      (node (ref "IC25") (pin "9") (pinfunction "A8_9") (pintype "bidirectional"))
    )
    (net (code "84") (name "PIA-B0") (class "Default")
      (node (ref "CORE-IO") (pin "13") (pinfunction "13_13") (pintype "passive"))
      (node (ref "IC26") (pin "2") (pinfunction "A1_2") (pintype "bidirectional"))
    )
    (net (code "85") (name "PIA-B1") (class "Default")
      (node (ref "CORE-IO") (pin "14") (pinfunction "14_14") (pintype "passive"))
      (node (ref "IC26") (pin "3") (pinfunction "A2_3") (pintype "bidirectional"))
    )
    (net (code "86") (name "PIA-B2") (class "Default")
      (node (ref "CORE-IO") (pin "15") (pinfunction "15_15") (pintype "passive"))
      (node (ref "IC26") (pin "4") (pinfunction "A3_4") (pintype "bidirectional"))
    )
    (net (code "87") (name "PIA-B3") (class "Default")
      (node (ref "CORE-IO") (pin "16") (pinfunction "16_16") (pintype "passive"))
      (node (ref "IC26") (pin "5") (pinfunction "A4_5") (pintype "bidirectional"))
    )
    (net (code "88") (name "PIA-B4") (class "Default")
      (node (ref "CORE-IO") (pin "17") (pinfunction "17_17") (pintype "passive"))
      (node (ref "IC26") (pin "6") (pinfunction "A5_6") (pintype "bidirectional"))
    )
    (net (code "89") (name "PIA-B5") (class "Default")
      (node (ref "CORE-IO") (pin "18") (pinfunction "18_18") (pintype "passive"))
      (node (ref "IC26") (pin "7") (pinfunction "A6_7") (pintype "bidirectional"))
    )
    (net (code "90") (name "PIA-B6") (class "Default")
      (node (ref "CORE-IO") (pin "19") (pinfunction "19_19") (pintype "passive"))
      (node (ref "IC26") (pin "8") (pinfunction "A7_8") (pintype "bidirectional"))
    )
    (net (code "91") (name "PIA-B7") (class "Default")
      (node (ref "CORE-IO") (pin "20") (pinfunction "20_20") (pintype "passive"))
      (node (ref "IC26") (pin "9") (pinfunction "A8_9") (pintype "bidirectional"))
    )
    (net (code "92") (name "Q") (class "Default")
      (node (ref "IC17") (pin "35") (pinfunction "Q_35") (pintype "input"))
      (node (ref "IC2") (pin "12") (pinfunction "Q_12") (pintype "output"))
      (node (ref "IC2") (pin "7") (pinfunction "J_7") (pintype "input"))
    )
    (net (code "93") (name "RX") (class "Default")
      (node (ref "IC20") (pin "12") (pinfunction "R1OUT_12") (pintype "output"))
      (node (ref "IC21") (pin "2") (pinfunction "RXDATA_2") (pintype "input"))
    )
    (net (code "94") (name "RXD") (class "Default")
      (node (ref "COM") (pin "3") (pinfunction "3_3") (pintype "passive"))
      (node (ref "IC20") (pin "13") (pinfunction "R1IN_13") (pintype "input"))
      (node (ref "RS-232") (pin "3") (pinfunction "3_3") (pintype "passive"))
    )
    (net (code "95") (name "R{slash}~{W}") (class "Default")
      (node (ref "IC17") (pin "32") (pinfunction "R/~{W}_32") (pintype "output"))
      (node (ref "IC21") (pin "13") (pinfunction "R/~{W}_13") (pintype "input"))
      (node (ref "IC22") (pin "27") (pinfunction "~{WE}_27") (pintype "input"))
      (node (ref "IC24") (pin "21") (pinfunction "R/~{W}_21") (pintype "input"))
    )
    (net (code "96") (name "TX") (class "Default")
      (node (ref "IC20") (pin "11") (pinfunction "T1IN_11") (pintype "input"))
      (node (ref "IC21") (pin "6") (pinfunction "TXDATA_6") (pintype "output"))
    )
    (net (code "97") (name "TXD") (class "Default")
      (node (ref "COM") (pin "2") (pinfunction "2_2") (pintype "passive"))
      (node (ref "IC20") (pin "14") (pinfunction "T1OUT_14") (pintype "output"))
      (node (ref "RS-232") (pin "1") (pinfunction "1_1") (pintype "passive"))
    )
    (net (code "98") (name "VCC") (class "Default")
      (node (ref "BYP17") (pin "1") (pinfunction "1_1") (pintype "passive"))
      (node (ref "BYP18") (pin "1") (pinfunction "1_1") (pintype "passive"))
      (node (ref "BYP19") (pin "1") (pinfunction "1_1") (pintype "passive"))
      (node (ref "BYP2") (pin "1") (pinfunction "1_1") (pintype "passive"))
      (node (ref "BYP20") (pin "1") (pinfunction "1_1") (pintype "passive"))
      (node (ref "BYP21") (pin "1") (pinfunction "1_1") (pintype "passive"))
      (node (ref "BYP22") (pin "1") (pinfunction "1_1") (pintype "passive"))
      (node (ref "BYP23") (pin "1") (pinfunction "1_1") (pintype "passive"))
      (node (ref "BYP24") (pin "1") (pinfunction "1_1") (pintype "passive"))
      (node (ref "BYP25") (pin "1") (pinfunction "1_1") (pintype "passive"))
      (node (ref "BYP26") (pin "1") (pinfunction "1_1") (pintype "passive"))
      (node (ref "BYP27") (pin "1") (pinfunction "1_1") (pintype "passive"))
      (node (ref "BYP28") (pin "1") (pinfunction "1_1") (pintype "passive"))
      (node (ref "BYP29") (pin "1") (pinfunction "1_1") (pintype "passive"))
      (node (ref "C10") (pin "1") (pinfunction "1_1") (pintype "passive"))
      (node (ref "CORE-IO") (pin "12") (pinfunction "12_12") (pintype "passive"))
      (node (ref "CORE-IO") (pin "9") (pinfunction "9_9") (pintype "passive"))
      (node (ref "IC17") (pin "7") (pinfunction "VCC_7") (pintype "power_in"))
      (node (ref "IC2") (pin "2") (pinfunction "CL_2") (pintype "input"))
      (node (ref "IC2") (pin "6") (pinfunction "CL_6") (pintype "input"))
      (node (ref "IC21") (pin "10") (pinfunction "CS1_10") (pintype "input"))
      (node (ref "IC21") (pin "12") (pinfunction "VCC_12") (pintype "power_in"))
      (node (ref "IC21") (pin "8") (pinfunction "CS0_8") (pintype "input"))
      (node (ref "IC22") (pin "28") (pinfunction "VCC_28") (pintype "power_in"))
      (node (ref "IC23") (pin "1") (pinfunction "VPP_1") (pintype "input"))
      (node (ref "IC23") (pin "27") (pinfunction "~{PGM}_27") (pintype "passive"))
      (node (ref "IC23") (pin "28") (pinfunction "VCC_28") (pintype "power_in"))
      (node (ref "IC24") (pin "20") (pinfunction "VCC_20") (pintype "power_in"))
      (node (ref "IC24") (pin "22") (pinfunction "CS0_22") (pintype "input"))
      (node (ref "IC24") (pin "24") (pinfunction "CS1_24") (pintype "input"))
      (node (ref "IC27") (pin "10") (pinfunction "R_10") (pintype "input"))
      (node (ref "IC27") (pin "14") (pinfunction "V+_14") (pintype "power_in"))
      (node (ref "IC27") (pin "4") (pinfunction "R_4") (pintype "input"))
      (node (ref "IC29") (pin "1") (pinfunction "VPP_1") (pintype "input"))
      (node (ref "JP2") (pin "2") (pinfunction "2_2") (pintype "passive"))
      (node (ref "JP4") (pin "2") (pinfunction "2_2") (pintype "passive"))
      (node (ref "QG1") (pin "14") (pinfunction "VCC_14") (pintype "power_in"))
      (node (ref "R1") (pin "2") (pinfunction "2_2") (pintype "passive"))
      (node (ref "R12") (pin "2") (pinfunction "2_2") (pintype "passive"))
      (node (ref "R14") (pin "2") (pinfunction "2_2") (pintype "passive"))
      (node (ref "R2") (pin "2") (pinfunction "2_2") (pintype "passive"))
      (node (ref "R3") (pin "2") (pinfunction "2_2") (pintype "passive"))
      (node (ref "R5") (pin "2") (pinfunction "2_2") (pintype "passive"))
      (node (ref "R6") (pin "2") (pinfunction "2_2") (pintype "passive"))
      (node (ref "R7") (pin "2") (pinfunction "2_2") (pintype "passive"))
      (node (ref "R8") (pin "2") (pinfunction "2_2") (pintype "passive"))
      (node (ref "R9") (pin "2") (pinfunction "2_2") (pintype "passive"))
    )
    (net (code "99") (name "unconnected-(COM-Pad1)") (class "Default")
      (node (ref "COM") (pin "1") (pinfunction "1_1") (pintype "passive"))
    )
    (net (code "100") (name "unconnected-(COM-Pad9)") (class "Default")
      (node (ref "COM") (pin "9") (pinfunction "9_9") (pintype "passive"))
    )
    (net (code "101") (name "unconnected-(IC17A-AVMA-Pad36)") (class "Default")
      (node (ref "IC17") (pin "36") (pinfunction "AVMA_36") (pintype "output"))
    )
    (net (code "102") (name "unconnected-(IC17A-BA-Pad6)") (class "Default")
      (node (ref "IC17") (pin "6") (pinfunction "BA_6") (pintype "output"))
    )
    (net (code "103") (name "unconnected-(IC17A-BS-Pad5)") (class "Default")
      (node (ref "IC17") (pin "5") (pinfunction "BS_5") (pintype "output"))
    )
    (net (code "104") (name "unconnected-(IC17A-BUSY-Pad33)") (class "Default")
      (node (ref "IC17") (pin "33") (pinfunction "BUSY_33") (pintype "output"))
    )
    (net (code "105") (name "unconnected-(IC17A-LIC-Pad38)") (class "Default")
      (node (ref "IC17") (pin "38") (pinfunction "LIC_38") (pintype "output"))
    )
    (net (code "106") (name "unconnected-(IC19A-Y0-Pad15)") (class "Default")
      (node (ref "IC19") (pin "15") (pinfunction "Y0_15") (pintype "output"))
    )
    (net (code "107") (name "unconnected-(IC19A-Y1-Pad14)") (class "Default")
      (node (ref "IC19") (pin "14") (pinfunction "Y1_14") (pintype "output"))
    )
    (net (code "108") (name "unconnected-(IC19A-Y2-Pad13)") (class "Default")
      (node (ref "IC19") (pin "13") (pinfunction "Y2_13") (pintype "output"))
    )
    (net (code "109") (name "unconnected-(IC19A-Y3-Pad12)") (class "Default")
      (node (ref "IC19") (pin "12") (pinfunction "Y3_12") (pintype "output"))
    )
    (net (code "110") (name "unconnected-(IC19A-Y4-Pad11)") (class "Default")
      (node (ref "IC19") (pin "11") (pinfunction "Y4_11") (pintype "output"))
    )
    (net (code "111") (name "unconnected-(IC19A-Y5-Pad10)") (class "Default")
      (node (ref "IC19") (pin "10") (pinfunction "Y5_10") (pintype "output"))
    )
    (net (code "112") (name "unconnected-(IC20A-R2OUT-Pad9)") (class "Default")
      (node (ref "IC20") (pin "9") (pinfunction "R2OUT_9") (pintype "output"))
    )
    (net (code "113") (name "unconnected-(IC22-NC-Pad1)") (class "Default")
      (node (ref "IC22") (pin "1") (pinfunction "NC_1") (pintype "no_connect"))
    )
    (net (code "114") (name "unconnected-(IC28A-Y1-Pad5)") (class "Default")
      (node (ref "IC28") (pin "5") (pinfunction "Y1_5") (pintype "output"))
    )
    (net (code "115") (name "unconnected-(IC28A-Y2-Pad6)") (class "Default")
      (node (ref "IC28") (pin "6") (pinfunction "Y2_6") (pintype "output"))
    )
    (net (code "116") (name "unconnected-(IC28B-Y0-Pad12)") (class "Default")
      (node (ref "IC28") (pin "12") (pinfunction "Y0_12") (pintype "output"))
    )
    (net (code "117") (name "~{4-B}") (class "Default")
      (node (ref "IC28") (pin "9") (pinfunction "Y3_9") (pintype "output"))
      (node (ref "IC29") (pin "20") (pinfunction "~{CE}_20") (pintype "input"))
      (node (ref "IC29") (pin "22") (pinfunction "~{OE}_22") (pintype "input"))
    )
    (net (code "118") (name "~{0123}") (class "Default")
      (node (ref "IC19") (pin "5") (pinfunction "G2B_5") (pintype "input"))
      (node (ref "IC22") (pin "20") (pinfunction "~{CS1}_20") (pintype "input"))
      (node (ref "IC22") (pin "22") (pinfunction "~{OE}_22") (pintype "input"))
      (node (ref "IC28") (pin "11") (pinfunction "Y1_11") (pintype "output"))
    )
    (net (code "119") (name "~{CDEF}") (class "Default")
      (node (ref "IC23") (pin "20") (pinfunction "~{CE}_20") (pintype "input"))
      (node (ref "IC23") (pin "22") (pinfunction "~{OE}_22") (pintype "input"))
      (node (ref "IC28") (pin "10") (pinfunction "Y2_10") (pintype "output"))
    )
    (net (code "120") (name "~{EP1}") (class "Default")
      (node (ref "IC28") (pin "14") (pinfunction "A_14") (pintype "input"))
      (node (ref "IC28") (pin "7") (pinfunction "Y3_7") (pintype "output"))
    )
    (net (code "121") (name "~{FIRQ}") (class "Default")
      (node (ref "IC17") (pin "4") (pinfunction "FIRQ_4") (pintype "input"))
      (node (ref "R8") (pin "1") (pinfunction "1_1") (pintype "passive"))
    )
    (net (code "122") (name "~{HLT}") (class "Default")
      (node (ref "IC17") (pin "40") (pinfunction "HALT_40") (pintype "input"))
      (node (ref "R5") (pin "1") (pinfunction "1_1") (pintype "passive"))
    )
    (net (code "123") (name "~{IO-E}") (class "Default")
      (node (ref "IC19") (pin "9") (pinfunction "Y6_9") (pintype "output"))
      (node (ref "IC24") (pin "23") (pinfunction "CS2_23") (pintype "input"))
    )
    (net (code "124") (name "~{IO-F}") (class "Default")
      (node (ref "IC19") (pin "7") (pinfunction "Y7_7") (pintype "output"))
      (node (ref "IC21") (pin "9") (pinfunction "CS2_9") (pintype "input"))
    )
    (net (code "125") (name "~{IRQ}") (class "Default")
      (node (ref "IC17") (pin "3") (pinfunction "IRQ_3") (pintype "input"))
      (node (ref "IC24") (pin "37") (pinfunction "IRQB_37") (pintype "open_collector"))
      (node (ref "IC24") (pin "38") (pinfunction "IRQA_38") (pintype "open_collector"))
      (node (ref "R7") (pin "1") (pinfunction "1_1") (pintype "passive"))
    )
    (net (code "126") (name "~{NMI}") (class "Default")
      (node (ref "IC17") (pin "2") (pinfunction "NMI_2") (pintype "input"))
      (node (ref "IC21") (pin "7") (pinfunction "IRQ_7") (pintype "output"))
      (node (ref "R6") (pin "1") (pinfunction "1_1") (pintype "passive"))
    )
    (net (code "127") (name "~{RST}") (class "Default")
      (node (ref "IC17") (pin "37") (pinfunction "RESET_37") (pintype "input"))
      (node (ref "IC18") (pin "6") (pinfunction "O_6") (pintype "output"))
      (node (ref "IC24") (pin "34") (pinfunction "RESET_34") (pintype "input"))
    )
  )
)
